# RST_SER_1.net
KiCad netlist of a schematic drawn in Altium Designer
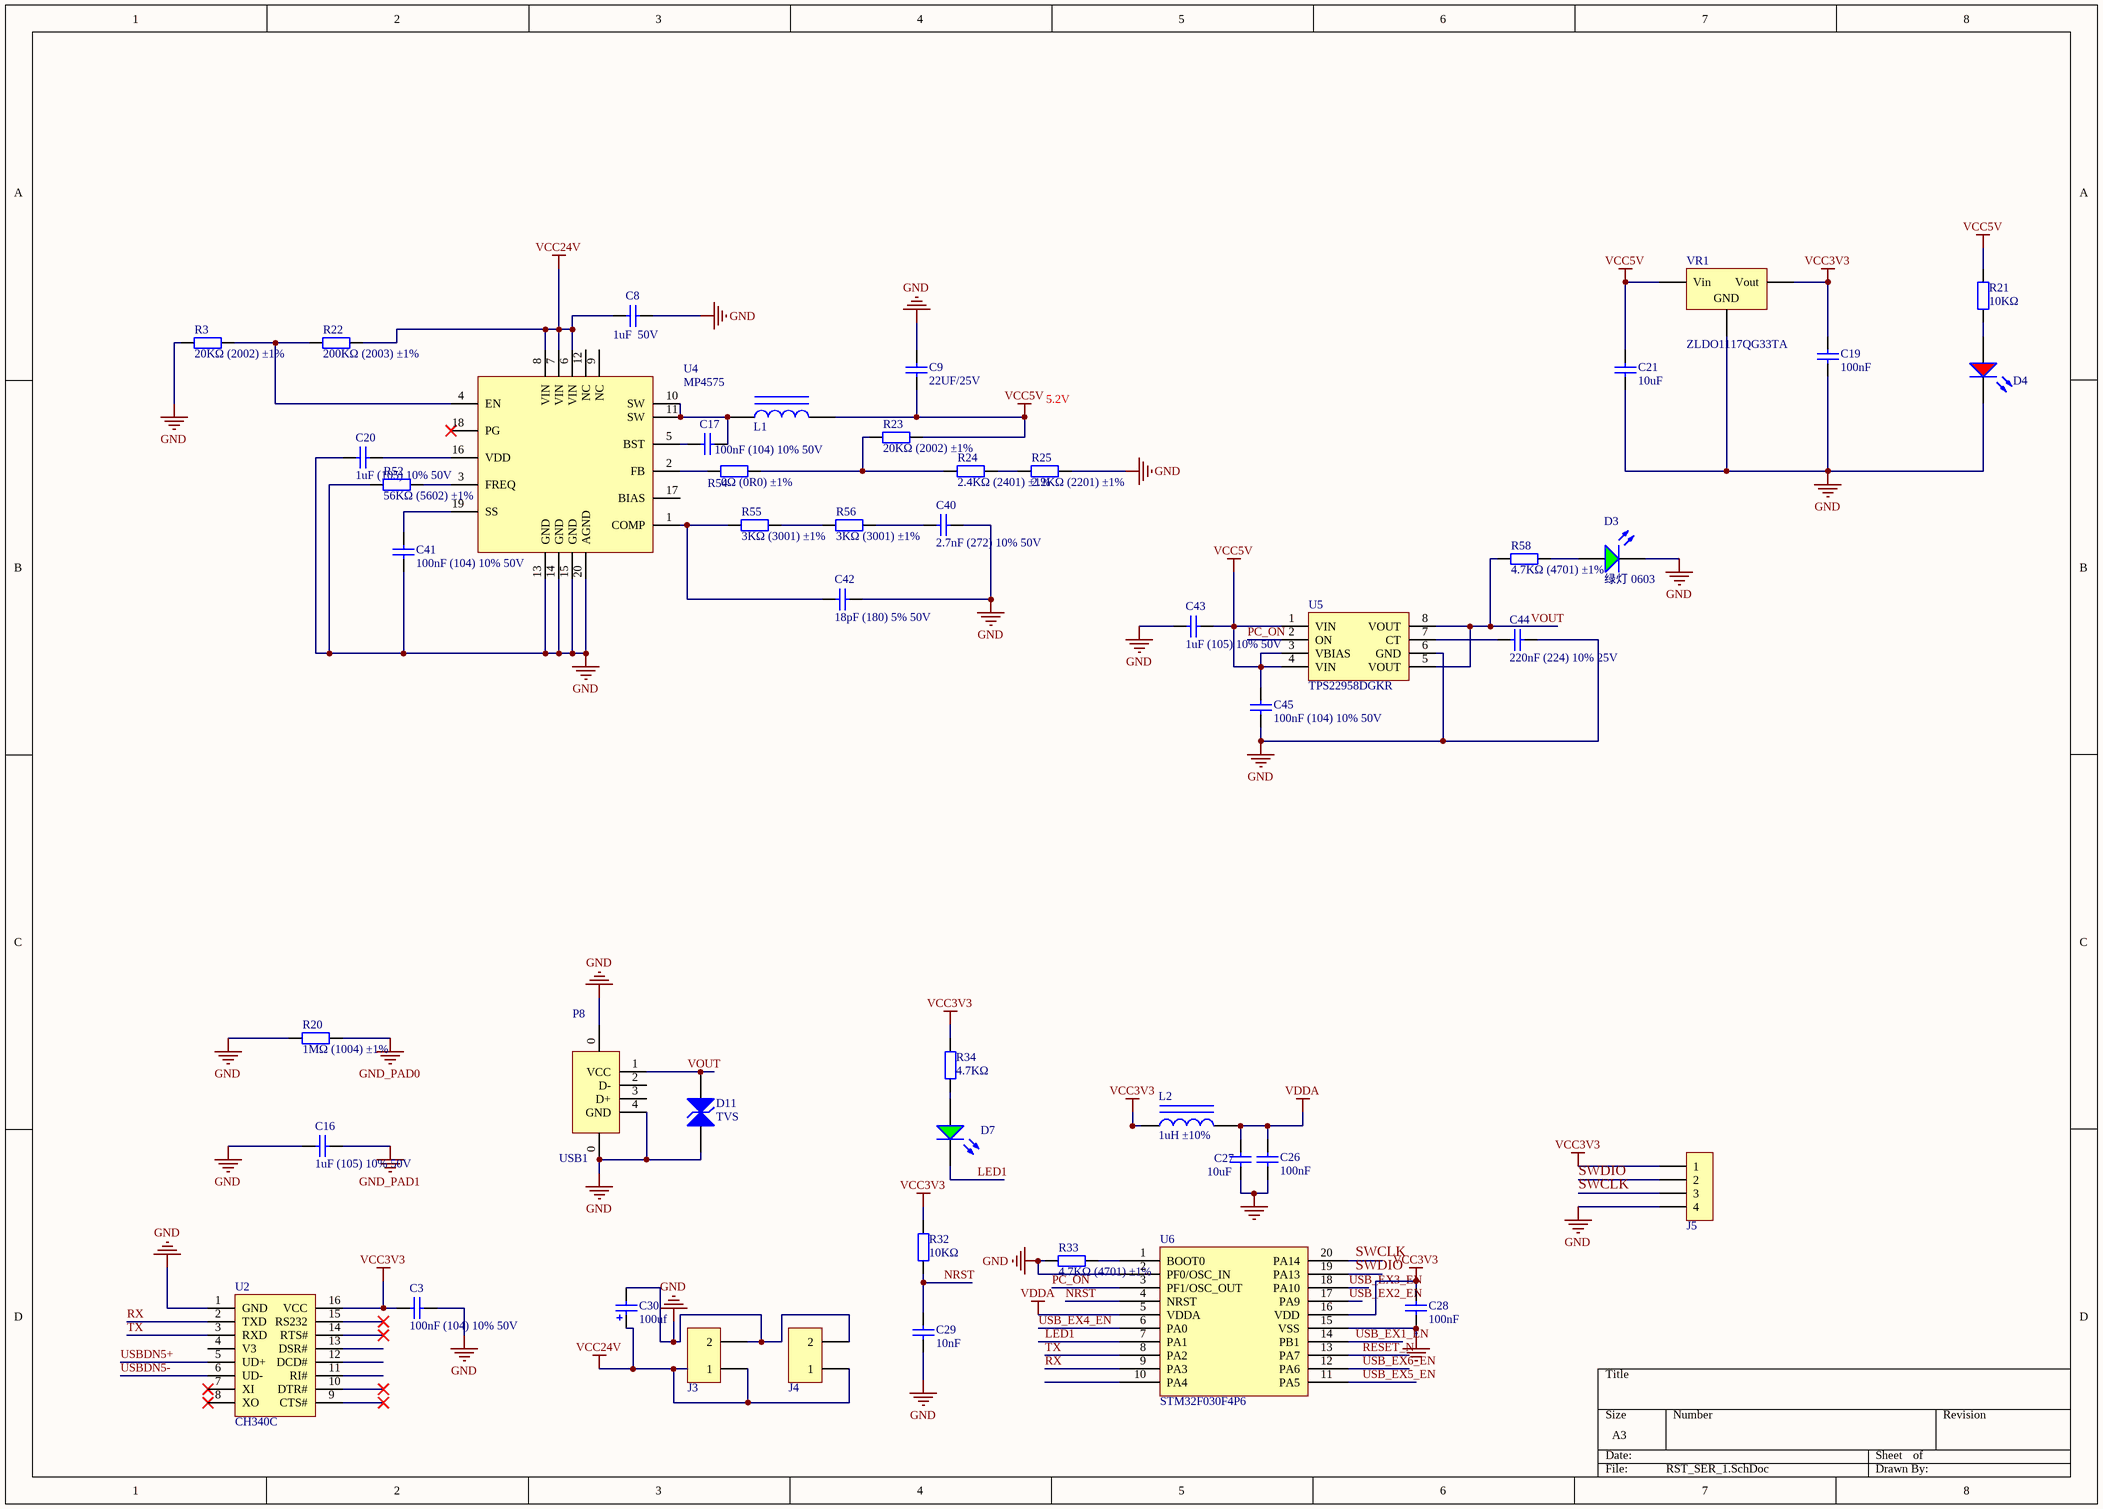
[diagram p0: RST_SER_1.SchDoc]

(export (version "E")
  (design (tool "Eeschema 10.0.6"))
  (components
    (comp (ref "C3")
      (value "100nF (104) 10% 50V")
      (footprint "0603_C")
      (description "贴片电容")
      (libsource (lib "AD封装2018.9.19Miscellaneous Devices LC") (part "0603 100nF (104) 10% 50V"))
    )
    (comp (ref "C8")
      (value "1uF  50V")
      (footprint "1206_C")
      (description "贴片电容")
      (libsource (lib "AD封装2018.9.19Miscellaneous Devices LC") (part "1206 1uF (105) 10% 50V"))
    )
    (comp (ref "C9")
      (value "22UF/25V")
      (footprint "1206_C")
      (description "贴片电容")
      (libsource (lib "AD封装2018.9.19Miscellaneous Devices LC") (part "1206 10uF (106) 10% 50V"))
    )
    (comp (ref "C16")
      (value "1uF (105) 10% 50V")
      (footprint "0603_C")
      (description "贴片电容")
      (libsource (lib "AD封装2018.9.19Miscellaneous Devices LC") (part "0603 1uF (105) 10% 50V"))
    )
    (comp (ref "C17")
      (value "100nF (104) 10% 50V")
      (footprint "0603_C")
      (description "贴片电容")
      (libsource (lib "AD封装2018.9.19Miscellaneous Devices LC") (part "0603 100nF (104) 10% 50V"))
    )
    (comp (ref "C19")
      (value "100nF")
      (footprint "0603_C")
      (description "贴片电容")
      (libsource (lib "AD封装2018.9.19Miscellaneous Devices LC") (part "0603 100nF (104) 10% 50V"))
    )
    (comp (ref "C20")
      (value "1uF (105) 10% 50V")
      (footprint "0603_C")
      (description "贴片电容")
      (libsource (lib "AD封装2018.9.19Miscellaneous Devices LC") (part "0603 1uF (105) 10% 50V"))
    )
    (comp (ref "C21")
      (value "10uF")
      (footprint "0603_C")
      (description "贴片电容")
      (libsource (lib "AD封装2018.9.19Miscellaneous Devices LC") (part "0603 10uF (106) 10% 10V"))
    )
    (comp (ref "C26")
      (value "100nF")
      (footprint "0603_C")
      (description "贴片电容")
      (libsource (lib "AD封装2018.9.19Miscellaneous Devices LC") (part "0603 100nF (104) 10% 50V"))
    )
    (comp (ref "C27")
      (value "10uF")
      (footprint "0603_C")
      (description "贴片电容")
      (libsource (lib "AD封装2018.9.19Miscellaneous Devices LC") (part "0603 10uF (106) 10% 10V"))
    )
    (comp (ref "C28")
      (value "100nF")
      (footprint "0603_C")
      (description "贴片电容")
      (libsource (lib "AD封装2018.9.19Miscellaneous Devices LC") (part "0603 100nF (104) 10% 50V"))
    )
    (comp (ref "C29")
      (value "10nF")
      (footprint "0603_C")
      (description "贴片电容")
      (libsource (lib "AD封装2018.9.19Miscellaneous Devices LC") (part "0603 10nF (103) 10% 50V"))
    )
    (comp (ref "C30") (value "100uf") (footprint "E_6.3*5.4") (libsource (lib "我的集成库") (part "C")))
    (comp (ref "C40")
      (value "2.7nF (272) 10% 50V")
      (footprint "0603_C")
      (description "贴片电容")
      (libsource (lib "AD封装2018.9.19Miscellaneous Devices LC") (part "0603 2.7nF (272) 10% 50V"))
    )
    (comp (ref "C41")
      (value "100nF (104) 10% 50V")
      (footprint "0603_C")
      (description "贴片电容")
      (libsource (lib "AD封装2018.9.19Miscellaneous Devices LC") (part "0603 100nF (104) 10% 50V"))
    )
    (comp (ref "C42")
      (value "18pF (180) 5% 50V")
      (footprint "0603_C")
      (description "贴片电容")
      (libsource (lib "AD封装2018.9.19Miscellaneous Devices LC") (part "0603 18pF (180) 5% 50V"))
    )
    (comp (ref "C43")
      (value "1uF (105) 10% 50V")
      (footprint "0603_C")
      (description "贴片电容")
      (libsource (lib "AD封装2018.9.19Miscellaneous Devices LC") (part "0603 1uF (105) 10% 50V"))
    )
    (comp (ref "C44")
      (value "220nF (224) 10% 25V")
      (footprint "0603_C")
      (description "贴片电容")
      (libsource (lib "AD封装2018.9.19Miscellaneous Devices LC") (part "0603 220nF (224) 10% 25V"))
    )
    (comp (ref "C45")
      (value "100nF (104) 10% 50V")
      (footprint "0603_C")
      (description "贴片电容")
      (libsource (lib "AD封装2018.9.19Miscellaneous Devices LC") (part "0603 100nF (104) 10% 50V"))
    )
    (comp (ref "D3")
      (value "绿灯 0603")
      (footprint "0603_LED_S1")
      (description "发光二极管")
      (libsource (lib "AD封装2018.9.19Miscellaneous Devices LC") (part "0603 绿灯"))
    )
    (comp (ref "D4")
      (value "红灯 0603")
      (footprint "0603_LED_S1")
      (description "发光二极管")
      (libsource (lib "AD封装2018.9.19Miscellaneous Devices LC") (part "0603 红灯"))
    )
    (comp (ref "D7")
      (value "绿灯 0603")
      (footprint "0603_LED_S1")
      (description "发光二极管")
      (libsource (lib "AD封装2018.9.19Miscellaneous Devices LC") (part "0603 绿灯"))
    )
    (comp (ref "D11") (value "TVS") (footprint "SOD-523") (libsource (lib "我的集成库") (part "TVS")))
    (comp (ref "J3") (value "MOTOR") (footprint "5557") (libsource (lib "我的集成库") (part "header2")))
    (comp (ref "J4") (value "MOTOR") (footprint "5557") (libsource (lib "我的集成库") (part "header2")))
    (comp (ref "J5") (value "header4") (footprint "xh-4") (libsource (lib "我的集成库") (part "header4")))
    (comp (ref "L1") (value "induct") (footprint "L_SMD,5.7x5.2mm") (libsource (lib "我的集成库") (part "induct")))
    (comp (ref "L2")
      (value "1uH ±10%")
      (footprint "0805_L")
      (description "贴片电感")
      (libsource (lib "IUD") (part "0805 100uH 10%"))
    )
    (comp (ref "P8")
      (value "USB1")
      (footprint "USB-A-TH_AF90-OFFSET - duplicate")
      (libsource (lib "我的集成库") (part "USB1"))
    )
    (comp (ref "R3")
      (value "20KΩ (2002) ±1%")
      (footprint "0603_R")
      (description "贴片电阻")
      (libsource (lib "AD封装2018.9.19Miscellaneous Devices LC") (part "0603 20KΩ (2002) 1%"))
    )
    (comp (ref "R20")
      (value "1MΩ (1004) ±1%")
      (footprint "0603_R")
      (description "贴片电阻")
      (libsource (lib "AD封装2018.9.19Miscellaneous Devices LC") (part "0603 1MΩ (1004) 1%"))
    )
    (comp (ref "R21")
      (value "10KΩ")
      (footprint "0603_R")
      (description "贴片电阻")
      (libsource (lib "AD封装2018.9.19Miscellaneous Devices LC") (part "0603 10KΩ (1002) 1%"))
    )
    (comp (ref "R22")
      (value "200KΩ (2003) ±1%")
      (footprint "0603_R")
      (description "贴片电阻")
      (libsource (lib "AD封装2018.9.19Miscellaneous Devices LC") (part "0603 200KΩ (2003) 1%"))
    )
    (comp (ref "R23")
      (value "20KΩ (2002) ±1%")
      (footprint "0603_R")
      (description "贴片电阻")
      (libsource (lib "AD封装2018.9.19Miscellaneous Devices LC") (part "0603 20KΩ (2002) 1%"))
    )
    (comp (ref "R24")
      (value "2.4KΩ (2401) ±1%")
      (footprint "0603_R")
      (description "贴片电阻")
      (libsource (lib "AD封装2018.9.19Miscellaneous Devices LC") (part "0603 2.4KΩ (2401) 1%"))
    )
    (comp (ref "R25")
      (value "2.2KΩ (2201) ±1%")
      (footprint "0603_R")
      (description "贴片电阻")
      (libsource (lib "AD封装2018.9.19Miscellaneous Devices LC") (part "0603 2.2KΩ (2201) 1%"))
    )
    (comp (ref "R32")
      (value "10KΩ")
      (footprint "0603_R")
      (description "贴片电阻")
      (libsource (lib "AD封装2018.9.19Miscellaneous Devices LC") (part "0603 10KΩ (1002) 1%"))
    )
    (comp (ref "R33")
      (value "4.7KΩ (4701) ±1%")
      (footprint "0603_R")
      (description "贴片电阻")
      (libsource (lib "AD封装2018.9.19Miscellaneous Devices LC") (part "0603 4.7KΩ (4701) 1%"))
    )
    (comp (ref "R34")
      (value "4.7KΩ")
      (footprint "0603_R")
      (description "贴片电阻")
      (libsource (lib "AD封装2018.9.19Miscellaneous Devices LC") (part "0603 1KΩ (1001) 1%"))
    )
    (comp (ref "R52")
      (value "56KΩ (5602) ±1%")
      (footprint "0603_R")
      (description "贴片电阻")
      (libsource (lib "AD封装2018.9.19Miscellaneous Devices LC") (part "0603 56KΩ (5602) 1%"))
    )
    (comp (ref "R54")
      (value "0Ω (0R0) ±1%")
      (footprint "0603_R")
      (description "贴片电阻")
      (libsource (lib "AD封装2018.9.19Miscellaneous Devices LC") (part "0603 0Ω (0R0) 1%"))
    )
    (comp (ref "R55")
      (value "3KΩ (3001) ±1%")
      (footprint "0603_R")
      (description "贴片电阻")
      (libsource (lib "AD封装2018.9.19Miscellaneous Devices LC") (part "0603 3KΩ (3001) 1%"))
    )
    (comp (ref "R56")
      (value "3KΩ (3001) ±1%")
      (footprint "0603_R")
      (description "贴片电阻")
      (libsource (lib "AD封装2018.9.19Miscellaneous Devices LC") (part "0603 3KΩ (3001) 1%"))
    )
    (comp (ref "R58")
      (value "4.7KΩ (4701) ±1%")
      (footprint "0603_R")
      (description "贴片电阻")
      (libsource (lib "AD封装2018.9.19Miscellaneous Devices LC") (part "0603 4.7KΩ (4701) 1%"))
    )
    (comp (ref "U2") (value "CH340C") (footprint "SOP-16") (libsource (lib "我的集成库") (part "CH340G")))
    (comp (ref "U4")
      (value "MP4575")
      (footprint "TSSOP-20")
      (description "MP4575_TSSOP-20")
      (libsource (lib "我的集成库") (part "MP4575"))
    )
    (comp (ref "U5")
      (value "TPS22958DGKR")
      (footprint "MSOP-8")
      (libsource (lib "我的集成库") (part "TPS22958DGKR"))
    )
    (comp (ref "U6")
      (value "STM32F030F4P6")
      (footprint "TSSOP-20")
      (description "ARM")
      (libsource (lib "AD封装2018.9.19Miscellaneous Devices LC") (part "STM32F030F4P6"))
    )
    (comp (ref "VR1")
      (value "ZLDO1117QG33TA")
      (footprint "SOT-223")
      (description "低压差线性稳压(LDO)")
      (libsource (lib "LDO") (part "SOT-223 AMS1117-3.3"))
    )
  )
  (nets
    (net (code "1") (name "/LED1") (class "Default")
      (node (ref "D7") (pin "K") (pinfunction "K_K") (pintype "passive"))
      (node (ref "U6") (pin "7") (pinfunction "PA1_7") (pintype "passive"))
    )
    (net (code "2") (name "/NRST") (class "Default")
      (node (ref "C29") (pin "2") (pinfunction "2_2") (pintype "passive"))
      (node (ref "R32") (pin "1") (pinfunction "1_1") (pintype "passive"))
      (node (ref "U6") (pin "4") (pinfunction "NRST_4") (pintype "passive"))
    )
    (net (code "3") (name "/PC_ON") (class "Default")
      (node (ref "U5") (pin "2") (pinfunction "ON_2") (pintype "passive"))
      (node (ref "U6") (pin "3") (pinfunction "PF1/OSC_OUT_3") (pintype "passive"))
    )
    (net (code "4") (name "/RESET_N") (class "Default")
      (node (ref "U6") (pin "13") (pinfunction "PA7_13") (pintype "passive"))
    )
    (net (code "5") (name "/RX") (class "Default")
      (node (ref "U2") (pin "2") (pinfunction "TXD_2") (pintype "passive"))
      (node (ref "U6") (pin "9") (pinfunction "PA3_9") (pintype "passive"))
    )
    (net (code "6") (name "/SWCLK") (class "Default")
      (node (ref "J5") (pin "3") (pinfunction "3_3") (pintype "passive"))
      (node (ref "U6") (pin "20") (pinfunction "PA14_20") (pintype "passive"))
    )
    (net (code "7") (name "/SWDIO") (class "Default")
      (node (ref "J5") (pin "2") (pinfunction "2_2") (pintype "passive"))
      (node (ref "U6") (pin "19") (pinfunction "PA13_19") (pintype "passive"))
    )
    (net (code "8") (name "/TX") (class "Default")
      (node (ref "U2") (pin "3") (pinfunction "RXD_3") (pintype "passive"))
      (node (ref "U6") (pin "8") (pinfunction "PA2_8") (pintype "passive"))
    )
    (net (code "9") (name "/USBDN5+") (class "Default")
      (node (ref "U2") (pin "5") (pinfunction "UD+_5") (pintype "passive"))
    )
    (net (code "10") (name "/USBDN5-") (class "Default")
      (node (ref "U2") (pin "6") (pinfunction "UD-_6") (pintype "passive"))
    )
    (net (code "11") (name "/USB_EX1_EN") (class "Default")
      (node (ref "U6") (pin "14") (pinfunction "PB1_14") (pintype "passive"))
    )
    (net (code "12") (name "/USB_EX2_EN") (class "Default")
      (node (ref "U6") (pin "17") (pinfunction "PA9_17") (pintype "passive"))
    )
    (net (code "13") (name "/USB_EX3_EN") (class "Default")
      (node (ref "U6") (pin "18") (pinfunction "PA10_18") (pintype "passive"))
    )
    (net (code "14") (name "/USB_EX4_EN") (class "Default")
      (node (ref "U6") (pin "6") (pinfunction "PA0_6") (pintype "passive"))
    )
    (net (code "15") (name "/USB_EX5_EN") (class "Default")
      (node (ref "U6") (pin "11") (pinfunction "PA5_11") (pintype "passive"))
    )
    (net (code "16") (name "/USB_EX6_EN") (class "Default")
      (node (ref "U6") (pin "12") (pinfunction "PA6_12") (pintype "passive"))
    )
    (net (code "17") (name "/VOUT") (class "Default")
      (node (ref "D11") (pin "2") (pinfunction "K_2") (pintype "passive"))
      (node (ref "P8") (pin "1") (pinfunction "VCC_1") (pintype "passive"))
      (node (ref "R58") (pin "1") (pinfunction "1_1") (pintype "passive"))
      (node (ref "U5") (pin "5") (pinfunction "VOUT_5") (pintype "passive"))
      (node (ref "U5") (pin "8") (pinfunction "VOUT_8") (pintype "passive"))
    )
    (net (code "18") (name "GND") (class "Default")
      (node (ref "C16") (pin "1") (pinfunction "1_1") (pintype "passive"))
      (node (ref "C19") (pin "1") (pinfunction "1_1") (pintype "passive"))
      (node (ref "C20") (pin "1") (pinfunction "1_1") (pintype "passive"))
      (node (ref "C21") (pin "1") (pinfunction "1_1") (pintype "passive"))
      (node (ref "C26") (pin "1") (pinfunction "1_1") (pintype "passive"))
      (node (ref "C27") (pin "1") (pinfunction "1_1") (pintype "passive"))
      (node (ref "C28") (pin "1") (pinfunction "1_1") (pintype "passive"))
      (node (ref "C29") (pin "1") (pinfunction "1_1") (pintype "passive"))
      (node (ref "C3") (pin "2") (pinfunction "2_2") (pintype "passive"))
      (node (ref "C30") (pin "2") (pinfunction "2_2") (pintype "passive"))
      (node (ref "C40") (pin "2") (pinfunction "2_2") (pintype "passive"))
      (node (ref "C41") (pin "1") (pinfunction "1_1") (pintype "passive"))
      (node (ref "C42") (pin "2") (pinfunction "2_2") (pintype "passive"))
      (node (ref "C43") (pin "1") (pinfunction "1_1") (pintype "passive"))
      (node (ref "C44") (pin "2") (pinfunction "2_2") (pintype "passive"))
      (node (ref "C45") (pin "1") (pinfunction "1_1") (pintype "passive"))
      (node (ref "C8") (pin "2") (pinfunction "2_2") (pintype "passive"))
      (node (ref "C9") (pin "2") (pinfunction "2_2") (pintype "passive"))
      (node (ref "D11") (pin "1") (pinfunction "A_1") (pintype "passive"))
      (node (ref "D3") (pin "K") (pinfunction "K_K") (pintype "passive"))
      (node (ref "D4") (pin "K") (pinfunction "K_K") (pintype "passive"))
      (node (ref "J3") (pin "2") (pinfunction "2_2") (pintype "passive"))
      (node (ref "J4") (pin "2") (pinfunction "2_2") (pintype "passive"))
      (node (ref "J5") (pin "4") (pinfunction "4_4") (pintype "passive"))
      (node (ref "P8") (pin "0") (pinfunction "0_0") (pintype "passive"))
      (node (ref "P8") (pin "4") (pinfunction "GND_4") (pintype "passive"))
      (node (ref "R20") (pin "1") (pinfunction "1_1") (pintype "passive"))
      (node (ref "R25") (pin "2") (pinfunction "2_2") (pintype "passive"))
      (node (ref "R3") (pin "1") (pinfunction "1_1") (pintype "passive"))
      (node (ref "R33") (pin "1") (pinfunction "1_1") (pintype "passive"))
      (node (ref "R52") (pin "1") (pinfunction "1_1") (pintype "passive"))
      (node (ref "U2") (pin "1") (pinfunction "GND_1") (pintype "power_in"))
      (node (ref "U4") (pin "13") (pinfunction "GND_13") (pintype "passive"))
      (node (ref "U4") (pin "14") (pinfunction "GND_14") (pintype "passive"))
      (node (ref "U4") (pin "15") (pinfunction "GND_15") (pintype "passive"))
      (node (ref "U4") (pin "20") (pinfunction "AGND_20") (pintype "passive"))
      (node (ref "U5") (pin "6") (pinfunction "GND_6") (pintype "passive"))
      (node (ref "U6") (pin "15") (pinfunction "VSS_15") (pintype "passive"))
      (node (ref "U6") (pin "2") (pinfunction "PF0/OSC_IN_2") (pintype "passive"))
      (node (ref "VR1") (pin "1") (pinfunction "GND_1") (pintype "passive"))
    )
    (net (code "19") (name "GND_PAD0") (class "Default")
      (node (ref "R20") (pin "2") (pinfunction "2_2") (pintype "passive"))
    )
    (net (code "20") (name "GND_PAD1") (class "Default")
      (node (ref "C16") (pin "2") (pinfunction "2_2") (pintype "passive"))
    )
    (net (code "21") (name "Net-(C17-Pad2)") (class "Default")
      (node (ref "C17") (pin "2") (pinfunction "2_2") (pintype "passive"))
      (node (ref "L1") (pin "1") (pinfunction "1_1") (pintype "passive"))
      (node (ref "U4") (pin "10") (pinfunction "SW_10") (pintype "passive"))
      (node (ref "U4") (pin "11") (pinfunction "SW_11") (pintype "passive"))
    )
    (net (code "22") (name "Net-(C40-Pad1)") (class "Default")
      (node (ref "C40") (pin "1") (pinfunction "1_1") (pintype "passive"))
      (node (ref "R56") (pin "2") (pinfunction "2_2") (pintype "passive"))
    )
    (net (code "23") (name "Net-(D3-PadA)") (class "Default")
      (node (ref "D3") (pin "A") (pinfunction "A_A") (pintype "passive"))
      (node (ref "R58") (pin "2") (pinfunction "2_2") (pintype "passive"))
    )
    (net (code "24") (name "Net-(D4-PadA)") (class "Default")
      (node (ref "D4") (pin "A") (pinfunction "A_A") (pintype "passive"))
      (node (ref "R21") (pin "1") (pinfunction "1_1") (pintype "passive"))
    )
    (net (code "25") (name "Net-(D7-PadA)") (class "Default")
      (node (ref "D7") (pin "A") (pinfunction "A_A") (pintype "passive"))
      (node (ref "R34") (pin "1") (pinfunction "1_1") (pintype "passive"))
    )
    (net (code "26") (name "Net-(R23-Pad1)") (class "Default")
      (node (ref "R23") (pin "1") (pinfunction "1_1") (pintype "passive"))
      (node (ref "R24") (pin "1") (pinfunction "1_1") (pintype "passive"))
      (node (ref "R54") (pin "2") (pinfunction "2_2") (pintype "passive"))
    )
    (net (code "27") (name "Net-(R24-Pad2)") (class "Default")
      (node (ref "R24") (pin "2") (pinfunction "2_2") (pintype "passive"))
      (node (ref "R25") (pin "1") (pinfunction "1_1") (pintype "passive"))
    )
    (net (code "28") (name "Net-(R55-Pad2)") (class "Default")
      (node (ref "R55") (pin "2") (pinfunction "2_2") (pintype "passive"))
      (node (ref "R56") (pin "1") (pinfunction "1_1") (pintype "passive"))
    )
    (net (code "29") (name "Net-(U4-BST)") (class "Default")
      (node (ref "C17") (pin "1") (pinfunction "1_1") (pintype "passive"))
      (node (ref "U4") (pin "5") (pinfunction "BST_5") (pintype "passive"))
    )
    (net (code "30") (name "Net-(U4-COMP)") (class "Default")
      (node (ref "C42") (pin "1") (pinfunction "1_1") (pintype "passive"))
      (node (ref "R55") (pin "1") (pinfunction "1_1") (pintype "passive"))
      (node (ref "U4") (pin "1") (pinfunction "COMP_1") (pintype "passive"))
    )
    (net (code "31") (name "Net-(U4-EN)") (class "Default")
      (node (ref "R22") (pin "1") (pinfunction "1_1") (pintype "passive"))
      (node (ref "R3") (pin "2") (pinfunction "2_2") (pintype "passive"))
      (node (ref "U4") (pin "4") (pinfunction "EN_4") (pintype "passive"))
    )
    (net (code "32") (name "Net-(U4-FB)") (class "Default")
      (node (ref "R54") (pin "1") (pinfunction "1_1") (pintype "passive"))
      (node (ref "U4") (pin "2") (pinfunction "FB_2") (pintype "passive"))
    )
    (net (code "33") (name "Net-(U4-FREQ)") (class "Default")
      (node (ref "R52") (pin "2") (pinfunction "2_2") (pintype "passive"))
      (node (ref "U4") (pin "3") (pinfunction "FREQ_3") (pintype "passive"))
    )
    (net (code "34") (name "Net-(U4-SS)") (class "Default")
      (node (ref "C41") (pin "2") (pinfunction "2_2") (pintype "passive"))
      (node (ref "U4") (pin "19") (pinfunction "SS_19") (pintype "passive"))
    )
    (net (code "35") (name "Net-(U4-VDD)") (class "Default")
      (node (ref "C20") (pin "2") (pinfunction "2_2") (pintype "passive"))
      (node (ref "U4") (pin "16") (pinfunction "VDD_16") (pintype "passive"))
    )
    (net (code "36") (name "Net-(U5-CT)") (class "Default")
      (node (ref "C44") (pin "1") (pinfunction "1_1") (pintype "passive"))
      (node (ref "U5") (pin "7") (pinfunction "CT_7") (pintype "passive"))
    )
    (net (code "37") (name "Net-(U6-BOOT0)") (class "Default")
      (node (ref "R33") (pin "2") (pinfunction "2_2") (pintype "passive"))
      (node (ref "U6") (pin "1") (pinfunction "BOOT0_1") (pintype "passive"))
    )
    (net (code "38") (name "VCC3V3") (class "Default")
      (node (ref "C19") (pin "2") (pinfunction "2_2") (pintype "passive"))
      (node (ref "C28") (pin "2") (pinfunction "2_2") (pintype "passive"))
      (node (ref "C3") (pin "1") (pinfunction "1_1") (pintype "passive"))
      (node (ref "J5") (pin "1") (pinfunction "1_1") (pintype "passive"))
      (node (ref "L2") (pin "1") (pinfunction "1_1") (pintype "passive"))
      (node (ref "R32") (pin "2") (pinfunction "2_2") (pintype "passive"))
      (node (ref "R34") (pin "2") (pinfunction "2_2") (pintype "passive"))
      (node (ref "U2") (pin "16") (pinfunction "VCC_16") (pintype "passive"))
      (node (ref "U6") (pin "16") (pinfunction "VDD_16") (pintype "passive"))
      (node (ref "VR1") (pin "2") (pinfunction "Vout_2") (pintype "passive"))
    )
    (net (code "39") (name "VCC5V") (class "Default")
      (node (ref "C21") (pin "2") (pinfunction "2_2") (pintype "passive"))
      (node (ref "C43") (pin "2") (pinfunction "2_2") (pintype "passive"))
      (node (ref "C45") (pin "2") (pinfunction "2_2") (pintype "passive"))
      (node (ref "C9") (pin "1") (pinfunction "1_1") (pintype "passive"))
      (node (ref "L1") (pin "2") (pinfunction "2_2") (pintype "passive"))
      (node (ref "R21") (pin "2") (pinfunction "2_2") (pintype "passive"))
      (node (ref "R23") (pin "2") (pinfunction "2_2") (pintype "passive"))
      (node (ref "U5") (pin "1") (pinfunction "VIN_1") (pintype "passive"))
      (node (ref "U5") (pin "3") (pinfunction "VBIAS_3") (pintype "passive"))
      (node (ref "U5") (pin "4") (pinfunction "VIN_4") (pintype "passive"))
      (node (ref "VR1") (pin "3") (pinfunction "Vin_3") (pintype "passive"))
    )
    (net (code "40") (name "VCC24V") (class "Default")
      (node (ref "C30") (pin "1") (pinfunction "1_1") (pintype "passive"))
      (node (ref "C8") (pin "1") (pinfunction "1_1") (pintype "passive"))
      (node (ref "J3") (pin "1") (pinfunction "1_1") (pintype "passive"))
      (node (ref "J4") (pin "1") (pinfunction "1_1") (pintype "passive"))
      (node (ref "R22") (pin "2") (pinfunction "2_2") (pintype "passive"))
      (node (ref "U4") (pin "6") (pinfunction "VIN_6") (pintype "passive"))
      (node (ref "U4") (pin "7") (pinfunction "VIN_7") (pintype "passive"))
      (node (ref "U4") (pin "8") (pinfunction "VIN_8") (pintype "passive"))
    )
    (net (code "41") (name "VDDA") (class "Default")
      (node (ref "C26") (pin "2") (pinfunction "2_2") (pintype "passive"))
      (node (ref "C27") (pin "2") (pinfunction "2_2") (pintype "passive"))
      (node (ref "L2") (pin "2") (pinfunction "2_2") (pintype "passive"))
      (node (ref "U6") (pin "5") (pinfunction "VDDA_5") (pintype "passive"))
    )
    (net (code "42") (name "unconnected-(P8-D+-Pad3)") (class "Default")
      (node (ref "P8") (pin "3") (pinfunction "D+_3") (pintype "passive"))
    )
    (net (code "43") (name "unconnected-(P8-D--Pad2)") (class "Default")
      (node (ref "P8") (pin "2") (pinfunction "D-_2") (pintype "passive"))
    )
    (net (code "44") (name "unconnected-(P8-Pad0)") (class "Default")
      (node (ref "P8") (pin "0") (pinfunction "0_0") (pintype "passive"))
    )
    (net (code "45") (name "unconnected-(U2-CTS#-Pad9)") (class "Default")
      (node (ref "U2") (pin "9") (pinfunction "CTS#_9") (pintype "passive+no_connect"))
    )
    (net (code "46") (name "unconnected-(U2-DCD#-Pad12)") (class "Default")
      (node (ref "U2") (pin "12") (pinfunction "DCD#_12") (pintype "passive"))
    )
    (net (code "47") (name "unconnected-(U2-DSR#-Pad13)") (class "Default")
      (node (ref "U2") (pin "13") (pinfunction "DSR#_13") (pintype "passive"))
    )
    (net (code "48") (name "unconnected-(U2-DTR#-Pad10)") (class "Default")
      (node (ref "U2") (pin "10") (pinfunction "DTR#_10") (pintype "passive+no_connect"))
    )
    (net (code "49") (name "unconnected-(U2-RI#-Pad11)") (class "Default")
      (node (ref "U2") (pin "11") (pinfunction "RI#_11") (pintype "passive"))
    )
    (net (code "50") (name "unconnected-(U2-RS232-Pad15)") (class "Default")
      (node (ref "U2") (pin "15") (pinfunction "RS232_15") (pintype "passive+no_connect"))
    )
    (net (code "51") (name "unconnected-(U2-RTS#-Pad14)") (class "Default")
      (node (ref "U2") (pin "14") (pinfunction "RTS#_14") (pintype "passive+no_connect"))
    )
    (net (code "52") (name "unconnected-(U2-V3-Pad4)") (class "Default")
      (node (ref "U2") (pin "4") (pinfunction "V3_4") (pintype "passive"))
    )
    (net (code "53") (name "unconnected-(U2-XI-Pad7)") (class "Default")
      (node (ref "U2") (pin "7") (pinfunction "XI_7") (pintype "passive+no_connect"))
    )
    (net (code "54") (name "unconnected-(U2-XO-Pad8)") (class "Default")
      (node (ref "U2") (pin "8") (pinfunction "XO_8") (pintype "passive+no_connect"))
    )
    (net (code "55") (name "unconnected-(U4-BIAS-Pad17)") (class "Default")
      (node (ref "U4") (pin "17") (pinfunction "BIAS_17") (pintype "passive"))
    )
    (net (code "56") (name "unconnected-(U4-NC-Pad9)") (class "Default")
      (node (ref "U4") (pin "9") (pinfunction "NC_9") (pintype "passive"))
    )
    (net (code "57") (name "unconnected-(U4-NC-Pad12)") (class "Default")
      (node (ref "U4") (pin "12") (pinfunction "NC_12") (pintype "passive"))
    )
    (net (code "58") (name "unconnected-(U4-PG-Pad18)") (class "Default")
      (node (ref "U4") (pin "18") (pinfunction "PG_18") (pintype "passive+no_connect"))
    )
    (net (code "59") (name "unconnected-(U6-PA4-Pad10)") (class "Default")
      (node (ref "U6") (pin "10") (pinfunction "PA4_10") (pintype "passive"))
    )
  )
)
